# bristol_longshot__1.net
KiCad netlist of a schematic drawn in EAGLE
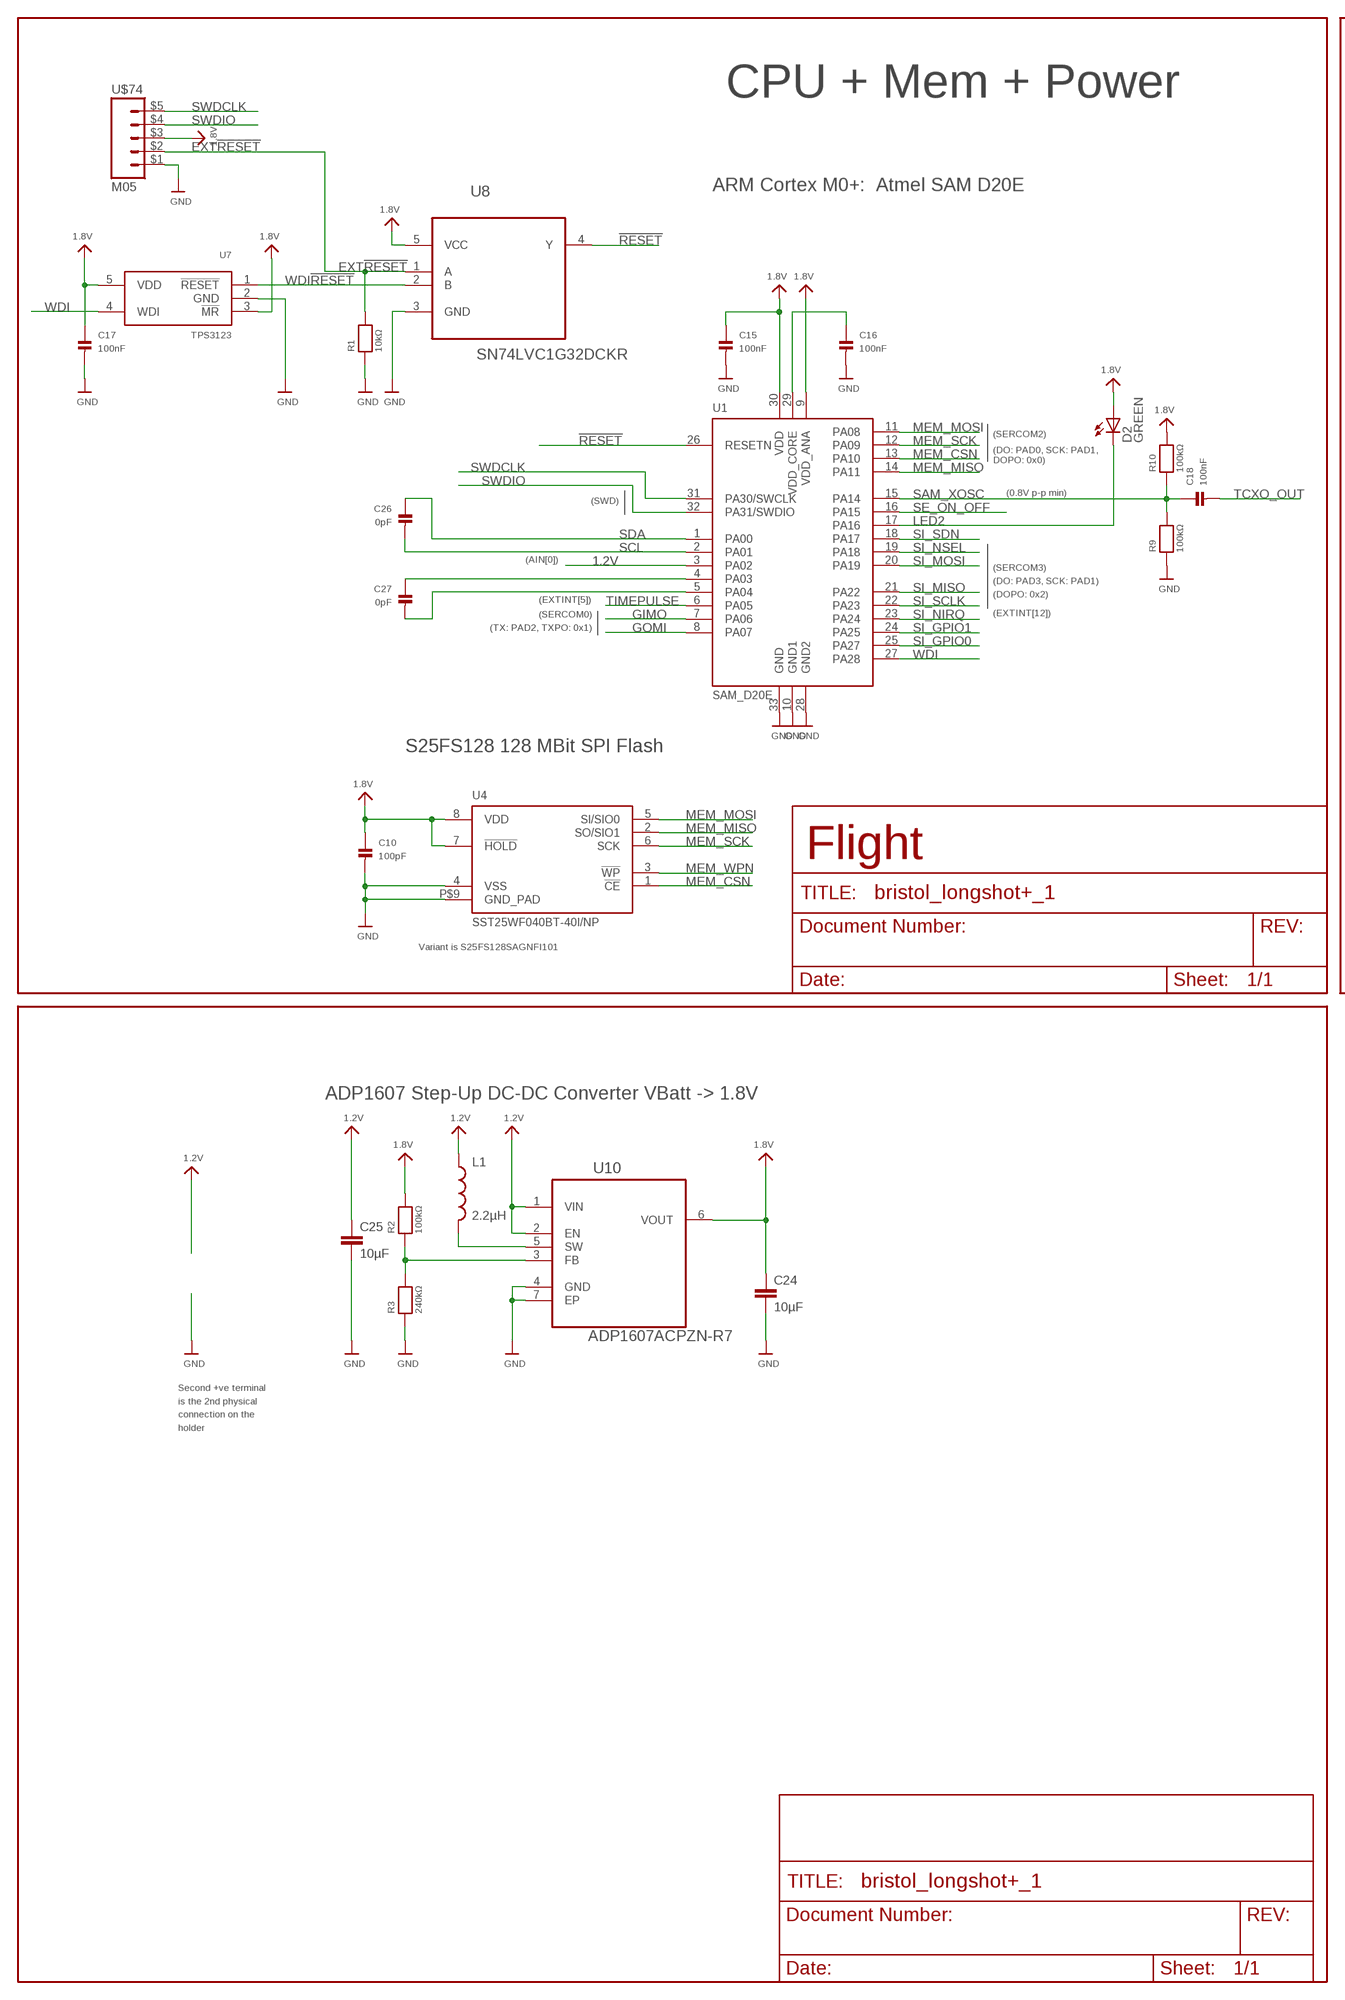
[diagram p0: schematic, sheet 1, part 1 of 2]
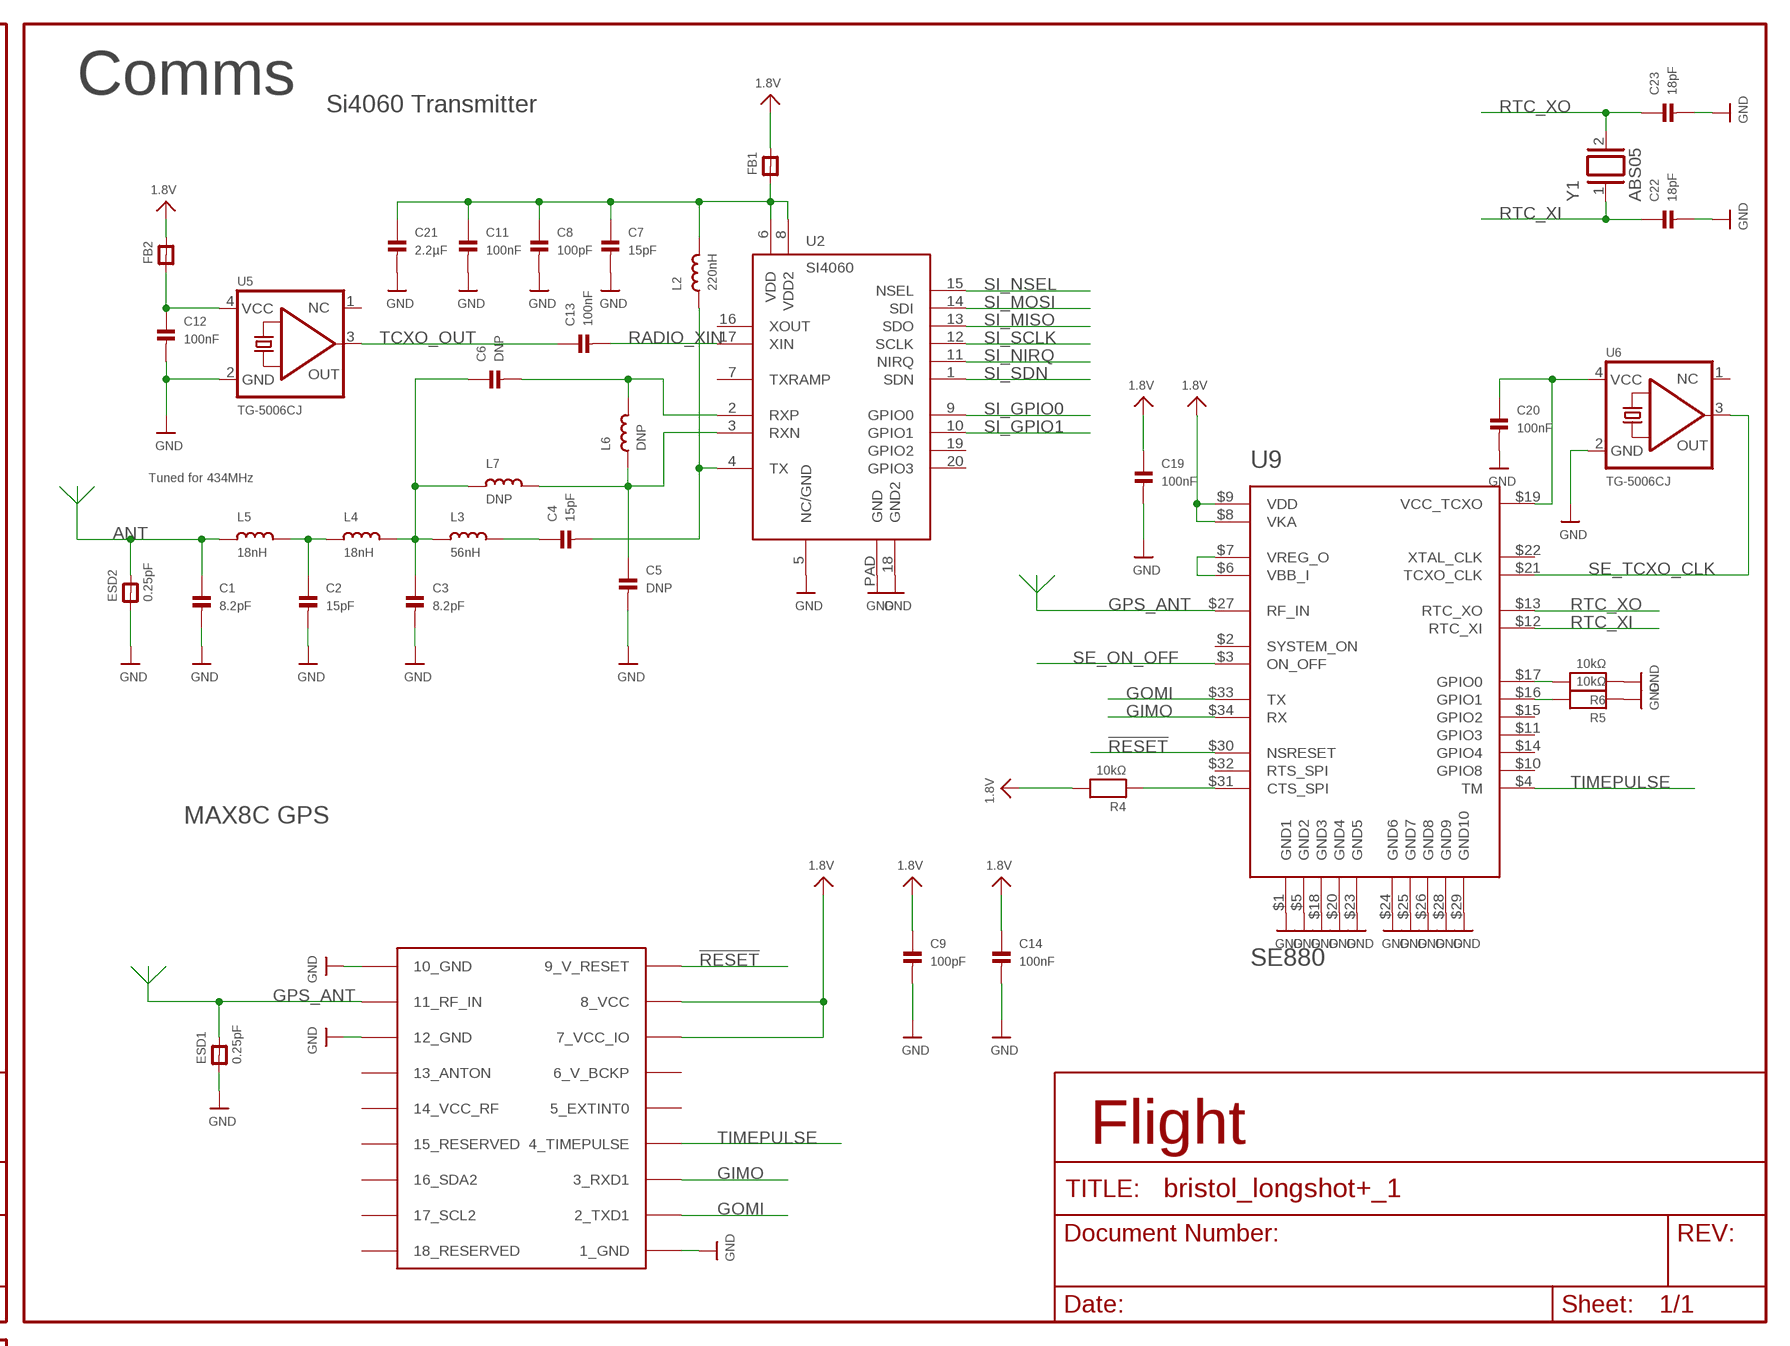
[diagram p1: schematic, sheet 1, part 2 of 2]

(export (version "E")
  (design (tool "Eeschema 10.0.6"))
  (components
    (comp (ref "C1")
      (value "8.2pF")
      (footprint "eagle-import:_0402")
      (libsource (lib "eagle-import") (part "CAP_CERAMIC_0402"))
    )
    (comp (ref "C2")
      (value "15pF")
      (footprint "eagle-import:_0402")
      (libsource (lib "eagle-import") (part "CAP_CERAMIC_0402"))
    )
    (comp (ref "C3")
      (value "8.2pF")
      (footprint "eagle-import:_0402")
      (libsource (lib "eagle-import") (part "CAP_CERAMIC_0402"))
    )
    (comp (ref "C4")
      (value "15pF")
      (footprint "eagle-import:_0402")
      (libsource (lib "eagle-import") (part "CAP_CERAMIC_0402"))
    )
    (comp (ref "C5")
      (value "DNP")
      (footprint "eagle-import:_0402")
      (libsource (lib "eagle-import") (part "CAP_CERAMIC_0402"))
    )
    (comp (ref "C6")
      (value "DNP")
      (footprint "eagle-import:_0402")
      (libsource (lib "eagle-import") (part "CAP_CERAMIC_0402"))
    )
    (comp (ref "C7")
      (value "15pF")
      (footprint "eagle-import:_0402")
      (libsource (lib "eagle-import") (part "CAP_CERAMIC_0402"))
    )
    (comp (ref "C8")
      (value "100pF")
      (footprint "eagle-import:_0402")
      (libsource (lib "eagle-import") (part "CAP_CERAMIC_0402"))
    )
    (comp (ref "C9")
      (value "100pF")
      (footprint "eagle-import:_0402")
      (libsource (lib "eagle-import") (part "CAP_CERAMIC_0402"))
    )
    (comp (ref "C10")
      (value "100pF")
      (footprint "eagle-import:_0402")
      (libsource (lib "eagle-import") (part "CAP_CERAMIC_0402"))
    )
    (comp (ref "C11")
      (value "100nF")
      (footprint "eagle-import:_0402")
      (libsource (lib "eagle-import") (part "CAP_CERAMIC_0402"))
    )
    (comp (ref "C12")
      (value "100nF")
      (footprint "eagle-import:_0402")
      (libsource (lib "eagle-import") (part "CAP_CERAMIC_0402"))
    )
    (comp (ref "C13")
      (value "100nF")
      (footprint "eagle-import:_0402")
      (libsource (lib "eagle-import") (part "CAP_CERAMIC_0402"))
    )
    (comp (ref "C14")
      (value "100nF")
      (footprint "eagle-import:_0402")
      (libsource (lib "eagle-import") (part "CAP_CERAMIC_0402"))
    )
    (comp (ref "C15")
      (value "100nF")
      (footprint "eagle-import:_0402")
      (libsource (lib "eagle-import") (part "CAP_CERAMIC_0402"))
    )
    (comp (ref "C16")
      (value "100nF")
      (footprint "eagle-import:_0402")
      (libsource (lib "eagle-import") (part "CAP_CERAMIC_0402"))
    )
    (comp (ref "C17")
      (value "100nF")
      (footprint "eagle-import:_0402")
      (libsource (lib "eagle-import") (part "CAP_CERAMIC_0402"))
    )
    (comp (ref "C18")
      (value "100nF")
      (footprint "eagle-import:_0402")
      (libsource (lib "eagle-import") (part "CAP_CERAMIC_0402"))
    )
    (comp (ref "C19")
      (value "100nF")
      (footprint "eagle-import:_0402")
      (libsource (lib "eagle-import") (part "CAP_CERAMIC_0402"))
    )
    (comp (ref "C20")
      (value "100nF")
      (footprint "eagle-import:_0402")
      (libsource (lib "eagle-import") (part "CAP_CERAMIC_0402"))
    )
    (comp (ref "C21")
      (value "2.2µF")
      (footprint "eagle-import:_0402")
      (libsource (lib "eagle-import") (part "CAP_CERAMIC_0402"))
    )
    (comp (ref "C22")
      (value "18pF")
      (footprint "eagle-import:_0402")
      (libsource (lib "eagle-import") (part "CAP_CERAMIC_0402"))
    )
    (comp (ref "C23")
      (value "18pF")
      (footprint "eagle-import:_0402")
      (libsource (lib "eagle-import") (part "CAP_CERAMIC_0402"))
    )
    (comp (ref "C24")
      (value "10µF")
      (footprint "eagle-import:C0603K")
      (libsource (lib "eagle-import") (part "C-EUC0603K"))
    )
    (comp (ref "C25")
      (value "10µF")
      (footprint "eagle-import:C0603K")
      (libsource (lib "eagle-import") (part "C-EUC0603K"))
    )
    (comp (ref "C26")
      (value "0pF")
      (footprint "eagle-import:_0402")
      (libsource (lib "eagle-import") (part "CAP_CERAMIC_0402"))
    )
    (comp (ref "C27")
      (value "0pF")
      (footprint "eagle-import:_0402")
      (libsource (lib "eagle-import") (part "CAP_CERAMIC_0402"))
    )
    (comp (ref "D2")
      (value "GREEN")
      (footprint "eagle-import:CHIPLED_0603")
      (libsource (lib "eagle-import") (part "LEDCHIPLED_0603"))
    )
    (comp (ref "ESD1")
      (value "0.25pF")
      (footprint "eagle-import:_0603MP")
      (libsource (lib "eagle-import") (part "FERRITE_0603MP"))
    )
    (comp (ref "ESD2")
      (value "0.25pF")
      (footprint "eagle-import:_0603MP")
      (libsource (lib "eagle-import") (part "FERRITE_0603MP"))
    )
    (comp (ref "FB1")
      (value "FERRITE_0402")
      (footprint "eagle-import:_0402")
      (libsource (lib "eagle-import") (part "FERRITE_0402"))
    )
    (comp (ref "FB2")
      (value "FERRITE_0402")
      (footprint "eagle-import:_0402")
      (libsource (lib "eagle-import") (part "FERRITE_0402"))
    )
    (comp (ref "L1")
      (value "2.2µH")
      (footprint "eagle-import:1007")
      (libsource (lib "eagle-import") (part "INDUCTOR1007"))
    )
    (comp (ref "L2")
      (value "220nH")
      (footprint "eagle-import:_0402")
      (libsource (lib "eagle-import") (part "INDUCTOR_0402"))
    )
    (comp (ref "L3")
      (value "56nH")
      (footprint "eagle-import:_0402")
      (libsource (lib "eagle-import") (part "INDUCTOR_0402"))
    )
    (comp (ref "L4")
      (value "18nH")
      (footprint "eagle-import:_0402")
      (libsource (lib "eagle-import") (part "INDUCTOR_0402"))
    )
    (comp (ref "L5")
      (value "18nH")
      (footprint "eagle-import:_0402")
      (libsource (lib "eagle-import") (part "INDUCTOR_0402"))
    )
    (comp (ref "L6")
      (value "DNP")
      (footprint "eagle-import:_0402")
      (libsource (lib "eagle-import") (part "INDUCTOR_0402"))
    )
    (comp (ref "L7")
      (value "DNP")
      (footprint "eagle-import:_0402")
      (libsource (lib "eagle-import") (part "INDUCTOR_0402"))
    )
    (comp (ref "R1")
      (value "10kΩ")
      (footprint "eagle-import:_0402")
      (libsource (lib "eagle-import") (part "RESISTOR_0402"))
    )
    (comp (ref "R2")
      (value "100kΩ")
      (footprint "eagle-import:_0402")
      (libsource (lib "eagle-import") (part "RESISTOR_0402"))
    )
    (comp (ref "R3")
      (value "240kΩ")
      (footprint "eagle-import:_0402")
      (libsource (lib "eagle-import") (part "RESISTOR_0402"))
    )
    (comp (ref "R4")
      (value "10kΩ")
      (footprint "eagle-import:_0402")
      (libsource (lib "eagle-import") (part "RESISTOR_0402"))
    )
    (comp (ref "R5")
      (value "10kΩ")
      (footprint "eagle-import:_0402")
      (libsource (lib "eagle-import") (part "RESISTOR_0402"))
    )
    (comp (ref "R6")
      (value "10kΩ")
      (footprint "eagle-import:_0402")
      (libsource (lib "eagle-import") (part "RESISTOR_0402"))
    )
    (comp (ref "R9")
      (value "100kΩ")
      (footprint "eagle-import:_0402")
      (libsource (lib "eagle-import") (part "RESISTOR_0402"))
    )
    (comp (ref "R10")
      (value "100kΩ")
      (footprint "eagle-import:_0402")
      (libsource (lib "eagle-import") (part "RESISTOR_0402"))
    )
    (comp (ref "U$74")
      (value "M05")
      (footprint "eagle-import:M05_SIDE")
      (libsource (lib "eagle-import") (part "M05"))
    )
    (comp (ref "U1")
      (value "SAM_D20E")
      (footprint "eagle-import:QFN32_5MM")
      (libsource (lib "eagle-import") (part "SAM_D20E"))
    )
    (comp (ref "U2")
      (value "SI4060")
      (footprint "eagle-import:QFN20")
      (libsource (lib "eagle-import") (part "SI4060"))
    )
    (comp (ref "U3")
      (value "UBLOX_MAX")
      (footprint "eagle-import:UBLOX_MAX")
      (libsource (lib "eagle-import") (part "UBLOX_MAX"))
    )
    (comp (ref "U4")
      (value "SST25WF040BT-40I/NP")
      (footprint "eagle-import:USON-8")
      (libsource (lib "eagle-import") (part "SST25WF040BT-40I/NP"))
    )
    (comp (ref "U5")
      (value "TG-5006CJ")
      (footprint "eagle-import:TC-5006CJ")
      (libsource (lib "eagle-import") (part "TG-5006CJ"))
    )
    (comp (ref "U6")
      (value "TG-5006CJ")
      (footprint "eagle-import:TC-5006CJ")
      (libsource (lib "eagle-import") (part "TG-5006CJ"))
    )
    (comp (ref "U7")
      (value "TPS3123")
      (footprint "eagle-import:SOT23-5")
      (libsource (lib "eagle-import") (part "TPS3123"))
    )
    (comp (ref "U8")
      (value "SN74LVC1G32DCKR")
      (footprint "eagle-import:SOT65P210X110-5N")
      (libsource (lib "eagle-import") (part "SN74LVC1G32DCKR"))
    )
    (comp (ref "U9")
      (value "SE880")
      (footprint "eagle-import:SE880")
      (libsource (lib "eagle-import") (part "SE880"))
    )
    (comp (ref "U10")
      (value "ADP1607ACPZN-R7")
      (footprint "eagle-import:DFN200X200X60-7N")
      (libsource (lib "eagle-import") (part "ADP1607ACPZN-R7"))
    )
    (comp (ref "Y1")
      (value "ABS05")
      (footprint "eagle-import:ABS05")
      (libsource (lib "eagle-import") (part "ABS05"))
    )
  )
  (nets
    (net (code "1") (name "/ANT") (class "Default")
      (node (ref "C1") (pin "1") (pinfunction "P$1_1") (pintype "passive"))
      (node (ref "ESD2") (pin "2") (pinfunction "P$2_2") (pintype "passive"))
      (node (ref "L5") (pin "1") (pinfunction "1_1") (pintype "passive"))
    )
    (net (code "2") (name "/EXT~{RESET}") (class "Default")
      (node (ref "R1") (pin "2") (pinfunction "2_2") (pintype "passive"))
      (node (ref "U$74") (pin "$2") (pinfunction "2_$2") (pintype "passive"))
      (node (ref "U8") (pin "1") (pinfunction "A_1") (pintype "input"))
    )
    (net (code "3") (name "/GIMO") (class "Default")
      (node (ref "U1") (pin "7") (pinfunction "PA06_7") (pintype "bidirectional"))
      (node (ref "U3") (pin "3_RXD1") (pinfunction "3_RXD1_3_RXD1") (pintype "bidirectional"))
      (node (ref "U9") (pin "$34") (pinfunction "RX_$34") (pintype "bidirectional"))
    )
    (net (code "4") (name "/GOMI") (class "Default")
      (node (ref "U1") (pin "8") (pinfunction "PA07_8") (pintype "bidirectional"))
      (node (ref "U3") (pin "2_TXD1") (pinfunction "2_TXD1_2_TXD1") (pintype "bidirectional"))
      (node (ref "U9") (pin "$33") (pinfunction "TX_$33") (pintype "bidirectional"))
    )
    (net (code "5") (name "/GPS_ANT") (class "Default")
      (node (ref "ESD1") (pin "2") (pinfunction "P$2_2") (pintype "passive"))
      (node (ref "U3") (pin "11_RF_IN") (pinfunction "11_RF_IN_11_RF_IN") (pintype "bidirectional"))
      (node (ref "U9") (pin "$27") (pinfunction "RF_IN_$27") (pintype "bidirectional"))
    )
    (net (code "6") (name "/LED2") (class "Default")
      (node (ref "D2") (pin "C") (pinfunction "C_C") (pintype "passive"))
      (node (ref "U1") (pin "17") (pinfunction "PA16_17") (pintype "bidirectional"))
    )
    (net (code "7") (name "/MEM_CSN") (class "Default")
      (node (ref "U1") (pin "13") (pinfunction "PA10_13") (pintype "bidirectional"))
      (node (ref "U4") (pin "1") (pinfunction "~{CE}_1") (pintype "input"))
    )
    (net (code "8") (name "/MEM_MISO") (class "Default")
      (node (ref "U1") (pin "14") (pinfunction "PA11_14") (pintype "bidirectional"))
      (node (ref "U4") (pin "2") (pinfunction "SO/SIO1_2") (pintype "output"))
    )
    (net (code "9") (name "/MEM_MOSI") (class "Default")
      (node (ref "U1") (pin "11") (pinfunction "PA08_11") (pintype "bidirectional"))
      (node (ref "U4") (pin "5") (pinfunction "SI/SIO0_5") (pintype "bidirectional"))
    )
    (net (code "10") (name "/MEM_SCK") (class "Default")
      (node (ref "U1") (pin "12") (pinfunction "PA09_12") (pintype "bidirectional"))
      (node (ref "U4") (pin "6") (pinfunction "SCK_6") (pintype "input"))
    )
    (net (code "11") (name "/MEM_WPN") (class "Default")
      (node (ref "U4") (pin "3") (pinfunction "~{WP}_3") (pintype "output"))
    )
    (net (code "12") (name "/RADIO_XIN") (class "Default")
      (node (ref "C13") (pin "2") (pinfunction "P$2_2") (pintype "passive"))
      (node (ref "U2") (pin "17") (pinfunction "XIN_17") (pintype "input"))
    )
    (net (code "13") (name "/RTC_XI") (class "Default")
      (node (ref "C22") (pin "1") (pinfunction "P$1_1") (pintype "passive"))
      (node (ref "U9") (pin "$12") (pinfunction "RTC_XI_$12") (pintype "bidirectional"))
      (node (ref "Y1") (pin "1") (pinfunction "1_1") (pintype "passive"))
    )
    (net (code "14") (name "/RTC_XO") (class "Default")
      (node (ref "C23") (pin "1") (pinfunction "P$1_1") (pintype "passive"))
      (node (ref "U9") (pin "$13") (pinfunction "RTC_XO_$13") (pintype "bidirectional"))
      (node (ref "Y1") (pin "2") (pinfunction "2_2") (pintype "passive"))
    )
    (net (code "15") (name "/SAM_XOSC") (class "Default")
      (node (ref "C18") (pin "1") (pinfunction "P$1_1") (pintype "passive"))
      (node (ref "R10") (pin "1") (pinfunction "1_1") (pintype "passive"))
      (node (ref "R9") (pin "2") (pinfunction "2_2") (pintype "passive"))
      (node (ref "U1") (pin "15") (pinfunction "PA14_15") (pintype "bidirectional"))
    )
    (net (code "16") (name "/SCL") (class "Default")
      (node (ref "C26") (pin "2") (pinfunction "P$2_2") (pintype "passive"))
      (node (ref "U1") (pin "2") (pinfunction "PA01_2") (pintype "bidirectional"))
    )
    (net (code "17") (name "/SDA") (class "Default")
      (node (ref "C26") (pin "1") (pinfunction "P$1_1") (pintype "passive"))
      (node (ref "U1") (pin "1") (pinfunction "PA00_1") (pintype "bidirectional"))
    )
    (net (code "18") (name "/SE_ON_OFF") (class "Default")
      (node (ref "U1") (pin "16") (pinfunction "PA15_16") (pintype "bidirectional"))
      (node (ref "U9") (pin "$3") (pinfunction "ON_OFF_$3") (pintype "bidirectional"))
    )
    (net (code "19") (name "/SE_TCXO_CLK") (class "Default")
      (node (ref "U6") (pin "3") (pinfunction "OUT_3") (pintype "output"))
      (node (ref "U9") (pin "$21") (pinfunction "TCXO_CLK_$21") (pintype "bidirectional"))
    )
    (net (code "20") (name "/SI_GPIO0") (class "Default")
      (node (ref "U1") (pin "25") (pinfunction "PA27_25") (pintype "bidirectional"))
      (node (ref "U2") (pin "9") (pinfunction "GPIO0_9") (pintype "bidirectional"))
    )
    (net (code "21") (name "/SI_GPIO1") (class "Default")
      (node (ref "U1") (pin "24") (pinfunction "PA25_24") (pintype "bidirectional"))
      (node (ref "U2") (pin "10") (pinfunction "GPIO1_10") (pintype "bidirectional"))
    )
    (net (code "22") (name "/SI_MISO") (class "Default")
      (node (ref "U1") (pin "21") (pinfunction "PA22_21") (pintype "bidirectional"))
      (node (ref "U2") (pin "13") (pinfunction "SDO_13") (pintype "output"))
    )
    (net (code "23") (name "/SI_MOSI") (class "Default")
      (node (ref "U1") (pin "20") (pinfunction "PA19_20") (pintype "bidirectional"))
      (node (ref "U2") (pin "14") (pinfunction "SDI_14") (pintype "bidirectional"))
    )
    (net (code "24") (name "/SI_NIRQ") (class "Default")
      (node (ref "U1") (pin "23") (pinfunction "PA24_23") (pintype "bidirectional"))
      (node (ref "U2") (pin "11") (pinfunction "NIRQ_11") (pintype "output"))
    )
    (net (code "25") (name "/SI_NSEL") (class "Default")
      (node (ref "U1") (pin "19") (pinfunction "PA18_19") (pintype "bidirectional"))
      (node (ref "U2") (pin "15") (pinfunction "NSEL_15") (pintype "input"))
    )
    (net (code "26") (name "/SI_SCLK") (class "Default")
      (node (ref "U1") (pin "22") (pinfunction "PA23_22") (pintype "bidirectional"))
      (node (ref "U2") (pin "12") (pinfunction "SCLK_12") (pintype "input"))
    )
    (net (code "27") (name "/SI_SDN") (class "Default")
      (node (ref "U1") (pin "18") (pinfunction "PA17_18") (pintype "bidirectional"))
      (node (ref "U2") (pin "1") (pinfunction "SDN_1") (pintype "input"))
    )
    (net (code "28") (name "/SWDCLK") (class "Default")
      (node (ref "U$74") (pin "$5") (pinfunction "5_$5") (pintype "passive"))
      (node (ref "U1") (pin "31") (pinfunction "PA30/SWCLK_31") (pintype "bidirectional"))
    )
    (net (code "29") (name "/SWDIO") (class "Default")
      (node (ref "U$74") (pin "$4") (pinfunction "4_$4") (pintype "passive"))
      (node (ref "U1") (pin "32") (pinfunction "PA31/SWDIO_32") (pintype "bidirectional"))
    )
    (net (code "30") (name "/TCXO_OUT") (class "Default")
      (node (ref "C13") (pin "1") (pinfunction "P$1_1") (pintype "passive"))
      (node (ref "C18") (pin "2") (pinfunction "P$2_2") (pintype "passive"))
      (node (ref "U5") (pin "3") (pinfunction "OUT_3") (pintype "output"))
    )
    (net (code "31") (name "/TIMEPULSE") (class "Default")
      (node (ref "U1") (pin "6") (pinfunction "PA05_6") (pintype "bidirectional"))
      (node (ref "U3") (pin "4_TIMEPULSE") (pinfunction "4_TIMEPULSE_4_TIMEPULSE") (pintype "bidirectional"))
      (node (ref "U9") (pin "$4") (pinfunction "TM_$4") (pintype "bidirectional"))
    )
    (net (code "32") (name "/WDI") (class "Default")
      (node (ref "U1") (pin "27") (pinfunction "PA28_27") (pintype "bidirectional"))
      (node (ref "U7") (pin "4") (pinfunction "WDI_4") (pintype "bidirectional"))
    )
    (net (code "33") (name "/WDI~{RESET}") (class "Default")
      (node (ref "U7") (pin "1") (pinfunction "~{RESET}_1") (pintype "bidirectional"))
      (node (ref "U8") (pin "2") (pinfunction "B_2") (pintype "input"))
    )
    (net (code "34") (name "/~{RESET}") (class "Default")
      (node (ref "U1") (pin "26") (pinfunction "RESETN_26") (pintype "input"))
      (node (ref "U3") (pin "9_V_RESET") (pinfunction "9_V_RESET_9_V_RESET") (pintype "power_in"))
      (node (ref "U8") (pin "4") (pinfunction "Y_4") (pintype "output"))
      (node (ref "U9") (pin "$30") (pinfunction "NSRESET_$30") (pintype "bidirectional"))
    )
    (net (code "35") (name "1.2V") (class "Default")
      (node (ref "C25") (pin "1") (pinfunction "1_1") (pintype "passive"))
      (node (ref "L1") (pin "1") (pinfunction "1_1") (pintype "passive"))
      (node (ref "U1") (pin "3") (pinfunction "PA02_3") (pintype "bidirectional"))
      (node (ref "U10") (pin "1") (pinfunction "VIN_1") (pintype "power_in"))
      (node (ref "U10") (pin "2") (pinfunction "EN_2") (pintype "input"))
    )
    (net (code "36") (name "1.8V") (class "Default")
      (node (ref "C10") (pin "1") (pinfunction "P$1_1") (pintype "passive"))
      (node (ref "C14") (pin "1") (pinfunction "P$1_1") (pintype "passive"))
      (node (ref "C15") (pin "1") (pinfunction "P$1_1") (pintype "passive"))
      (node (ref "C17") (pin "1") (pinfunction "P$1_1") (pintype "passive"))
      (node (ref "C19") (pin "1") (pinfunction "P$1_1") (pintype "passive"))
      (node (ref "C24") (pin "1") (pinfunction "1_1") (pintype "passive"))
      (node (ref "C9") (pin "1") (pinfunction "P$1_1") (pintype "passive"))
      (node (ref "D2") (pin "A") (pinfunction "A_A") (pintype "passive"))
      (node (ref "FB1") (pin "2") (pinfunction "P$2_2") (pintype "passive"))
      (node (ref "FB2") (pin "2") (pinfunction "P$2_2") (pintype "passive"))
      (node (ref "R10") (pin "2") (pinfunction "2_2") (pintype "passive"))
      (node (ref "R2") (pin "2") (pinfunction "2_2") (pintype "passive"))
      (node (ref "R4") (pin "2") (pinfunction "2_2") (pintype "passive"))
      (node (ref "U$74") (pin "$3") (pinfunction "3_$3") (pintype "passive"))
      (node (ref "U1") (pin "30") (pinfunction "VDD_30") (pintype "power_in"))
      (node (ref "U1") (pin "9") (pinfunction "VDD_ANA_9") (pintype "power_in"))
      (node (ref "U10") (pin "6") (pinfunction "VOUT_6") (pintype "output"))
      (node (ref "U3") (pin "7_VCC_IO") (pinfunction "7_VCC_IO_7_VCC_IO") (pintype "power_in"))
      (node (ref "U3") (pin "8_VCC") (pinfunction "8_VCC_8_VCC") (pintype "power_in"))
      (node (ref "U4") (pin "7") (pinfunction "~{HOLD}_7") (pintype "output"))
      (node (ref "U4") (pin "8") (pinfunction "VDD_8") (pintype "power_in"))
      (node (ref "U7") (pin "3") (pinfunction "~{MR}_3") (pintype "bidirectional"))
      (node (ref "U7") (pin "5") (pinfunction "VDD_5") (pintype "bidirectional"))
      (node (ref "U8") (pin "5") (pinfunction "VCC_5") (pintype "power_in"))
      (node (ref "U9") (pin "$8") (pinfunction "VKA_$8") (pintype "bidirectional"))
      (node (ref "U9") (pin "$9") (pinfunction "VDD_$9") (pintype "bidirectional"))
    )
    (net (code "37") (name "GND") (class "Default")
      (node (ref "C1") (pin "2") (pinfunction "P$2_2") (pintype "passive"))
      (node (ref "C10") (pin "2") (pinfunction "P$2_2") (pintype "passive"))
      (node (ref "C11") (pin "2") (pinfunction "P$2_2") (pintype "passive"))
      (node (ref "C12") (pin "2") (pinfunction "P$2_2") (pintype "passive"))
      (node (ref "C14") (pin "2") (pinfunction "P$2_2") (pintype "passive"))
      (node (ref "C15") (pin "2") (pinfunction "P$2_2") (pintype "passive"))
      (node (ref "C16") (pin "2") (pinfunction "P$2_2") (pintype "passive"))
      (node (ref "C17") (pin "2") (pinfunction "P$2_2") (pintype "passive"))
      (node (ref "C19") (pin "2") (pinfunction "P$2_2") (pintype "passive"))
      (node (ref "C2") (pin "2") (pinfunction "P$2_2") (pintype "passive"))
      (node (ref "C20") (pin "2") (pinfunction "P$2_2") (pintype "passive"))
      (node (ref "C21") (pin "2") (pinfunction "P$2_2") (pintype "passive"))
      (node (ref "C22") (pin "2") (pinfunction "P$2_2") (pintype "passive"))
      (node (ref "C23") (pin "2") (pinfunction "P$2_2") (pintype "passive"))
      (node (ref "C24") (pin "2") (pinfunction "2_2") (pintype "passive"))
      (node (ref "C25") (pin "2") (pinfunction "2_2") (pintype "passive"))
      (node (ref "C3") (pin "2") (pinfunction "P$2_2") (pintype "passive"))
      (node (ref "C5") (pin "2") (pinfunction "P$2_2") (pintype "passive"))
      (node (ref "C7") (pin "2") (pinfunction "P$2_2") (pintype "passive"))
      (node (ref "C8") (pin "2") (pinfunction "P$2_2") (pintype "passive"))
      (node (ref "C9") (pin "2") (pinfunction "P$2_2") (pintype "passive"))
      (node (ref "ESD1") (pin "1") (pinfunction "P$1_1") (pintype "passive"))
      (node (ref "ESD2") (pin "1") (pinfunction "P$1_1") (pintype "passive"))
      (node (ref "R1") (pin "1") (pinfunction "1_1") (pintype "passive"))
      (node (ref "R3") (pin "1") (pinfunction "1_1") (pintype "passive"))
      (node (ref "R5") (pin "1") (pinfunction "1_1") (pintype "passive"))
      (node (ref "R6") (pin "1") (pinfunction "1_1") (pintype "passive"))
      (node (ref "R9") (pin "1") (pinfunction "1_1") (pintype "passive"))
      (node (ref "U$74") (pin "$1") (pinfunction "1_$1") (pintype "passive"))
      (node (ref "U1") (pin "10") (pinfunction "GND1_10") (pintype "power_in"))
      (node (ref "U1") (pin "28") (pinfunction "GND2_28") (pintype "power_in"))
      (node (ref "U1") (pin "33") (pinfunction "GND_33") (pintype "power_in"))
      (node (ref "U10") (pin "4") (pinfunction "GND_4") (pintype "power_in"))
      (node (ref "U10") (pin "7") (pinfunction "EP_7") (pintype "passive"))
      (node (ref "U2") (pin "18") (pinfunction "GND2_18") (pintype "power_in"))
      (node (ref "U2") (pin "5") (pinfunction "NC/GND_5") (pintype "bidirectional"))
      (node (ref "U2") (pin "PAD") (pinfunction "GND_PAD") (pintype "power_in"))
      (node (ref "U3") (pin "10_GND") (pinfunction "10_GND_10_GND") (pintype "power_in"))
      (node (ref "U3") (pin "12_GND") (pinfunction "12_GND_12_GND") (pintype "power_in"))
      (node (ref "U3") (pin "1_GND") (pinfunction "1_GND_1_GND") (pintype "power_in"))
      (node (ref "U4") (pin "4") (pinfunction "VSS_4") (pintype "power_in"))
      (node (ref "U4") (pin "P$9") (pinfunction "GND_PAD_P$9") (pintype "power_in"))
      (node (ref "U5") (pin "2") (pinfunction "GND_2") (pintype "power_in"))
      (node (ref "U6") (pin "2") (pinfunction "GND_2") (pintype "power_in"))
      (node (ref "U7") (pin "2") (pinfunction "GND_2") (pintype "bidirectional"))
      (node (ref "U8") (pin "3") (pinfunction "GND_3") (pintype "passive"))
      (node (ref "U9") (pin "$1") (pinfunction "GND1_$1") (pintype "bidirectional"))
      (node (ref "U9") (pin "$18") (pinfunction "GND3_$18") (pintype "bidirectional"))
      (node (ref "U9") (pin "$20") (pinfunction "GND4_$20") (pintype "bidirectional"))
      (node (ref "U9") (pin "$23") (pinfunction "GND5_$23") (pintype "bidirectional"))
      (node (ref "U9") (pin "$24") (pinfunction "GND6_$24") (pintype "bidirectional"))
      (node (ref "U9") (pin "$25") (pinfunction "GND7_$25") (pintype "bidirectional"))
      (node (ref "U9") (pin "$26") (pinfunction "GND8_$26") (pintype "bidirectional"))
      (node (ref "U9") (pin "$28") (pinfunction "GND9_$28") (pintype "bidirectional"))
      (node (ref "U9") (pin "$29") (pinfunction "GND10_$29") (pintype "bidirectional"))
      (node (ref "U9") (pin "$5") (pinfunction "GND2_$5") (pintype "bidirectional"))
    )
    (net (code "38") (name "Net-(C2-P$1)") (class "Default")
      (node (ref "C2") (pin "1") (pinfunction "P$1_1") (pintype "passive"))
      (node (ref "L4") (pin "1") (pinfunction "1_1") (pintype "passive"))
      (node (ref "L5") (pin "2") (pinfunction "2_2") (pintype "passive"))
    )
    (net (code "39") (name "Net-(C3-P$1)") (class "Default")
      (node (ref "C3") (pin "1") (pinfunction "P$1_1") (pintype "passive"))
      (node (ref "C6") (pin "1") (pinfunction "P$1_1") (pintype "passive"))
      (node (ref "L3") (pin "1") (pinfunction "1_1") (pintype "passive"))
      (node (ref "L4") (pin "2") (pinfunction "2_2") (pintype "passive"))
      (node (ref "L7") (pin "1") (pinfunction "1_1") (pintype "passive"))
    )
    (net (code "40") (name "Net-(C4-P$1)") (class "Default")
      (node (ref "C4") (pin "1") (pinfunction "P$1_1") (pintype "passive"))
      (node (ref "L3") (pin "2") (pinfunction "2_2") (pintype "passive"))
    )
    (net (code "41") (name "Net-(C4-P$2)") (class "Default")
      (node (ref "C4") (pin "2") (pinfunction "P$2_2") (pintype "passive"))
      (node (ref "L2") (pin "1") (pinfunction "1_1") (pintype "passive"))
      (node (ref "U2") (pin "4") (pinfunction "TX_4") (pintype "output"))
    )
    (net (code "42") (name "Net-(C5-P$1)") (class "Default")
      (node (ref "C5") (pin "1") (pinfunction "P$1_1") (pintype "passive"))
      (node (ref "L6") (pin "1") (pinfunction "1_1") (pintype "passive"))
      (node (ref "L7") (pin "2") (pinfunction "2_2") (pintype "passive"))
      (node (ref "U2") (pin "3") (pinfunction "RXN_3") (pintype "input"))
    )
    (net (code "43") (name "Net-(C6-P$2)") (class "Default")
      (node (ref "C6") (pin "2") (pinfunction "P$2_2") (pintype "passive"))
      (node (ref "L6") (pin "2") (pinfunction "2_2") (pintype "passive"))
      (node (ref "U2") (pin "2") (pinfunction "RXP_2") (pintype "input"))
    )
    (net (code "44") (name "Net-(C11-P$1)") (class "Default")
      (node (ref "C11") (pin "1") (pinfunction "P$1_1") (pintype "passive"))
      (node (ref "C21") (pin "1") (pinfunction "P$1_1") (pintype "passive"))
      (node (ref "C7") (pin "1") (pinfunction "P$1_1") (pintype "passive"))
      (node (ref "C8") (pin "1") (pinfunction "P$1_1") (pintype "passive"))
      (node (ref "FB1") (pin "1") (pinfunction "P$1_1") (pintype "passive"))
      (node (ref "L2") (pin "2") (pinfunction "2_2") (pintype "passive"))
      (node (ref "U2") (pin "6") (pinfunction "VDD_6") (pintype "power_in"))
      (node (ref "U2") (pin "8") (pinfunction "VDD2_8") (pintype "power_in"))
    )
    (net (code "45") (name "Net-(C12-P$1)") (class "Default")
      (node (ref "C12") (pin "1") (pinfunction "P$1_1") (pintype "passive"))
      (node (ref "FB2") (pin "1") (pinfunction "P$1_1") (pintype "passive"))
      (node (ref "U5") (pin "4") (pinfunction "VCC_4") (pintype "power_in"))
    )
    (net (code "46") (name "Net-(C16-P$1)") (class "Default")
      (node (ref "C16") (pin "1") (pinfunction "P$1_1") (pintype "passive"))
      (node (ref "U1") (pin "29") (pinfunction "VDD_CORE_29") (pintype "power_in"))
    )
    (net (code "47") (name "Net-(C20-P$1)") (class "Default")
      (node (ref "C20") (pin "1") (pinfunction "P$1_1") (pintype "passive"))
      (node (ref "U6") (pin "4") (pinfunction "VCC_4") (pintype "power_in"))
      (node (ref "U9") (pin "$19") (pinfunction "VCC_TCXO_$19") (pintype "bidirectional"))
    )
    (net (code "48") (name "Net-(C27-P$1)") (class "Default")
      (node (ref "C27") (pin "1") (pinfunction "P$1_1") (pintype "passive"))
      (node (ref "U1") (pin "4") (pinfunction "PA03_4") (pintype "bidirectional"))
    )
    (net (code "49") (name "Net-(C27-P$2)") (class "Default")
      (node (ref "C27") (pin "2") (pinfunction "P$2_2") (pintype "passive"))
      (node (ref "U1") (pin "5") (pinfunction "PA04_5") (pintype "bidirectional"))
    )
    (net (code "50") (name "Net-(U9-CTS_SPI)") (class "Default")
      (node (ref "R4") (pin "1") (pinfunction "1_1") (pintype "passive"))
      (node (ref "U9") (pin "$31") (pinfunction "CTS_SPI_$31") (pintype "bidirectional"))
    )
    (net (code "51") (name "Net-(U9-GPIO0)") (class "Default")
      (node (ref "R6") (pin "2") (pinfunction "2_2") (pintype "passive"))
      (node (ref "U9") (pin "$17") (pinfunction "GPIO0_$17") (pintype "bidirectional"))
    )
    (net (code "52") (name "Net-(U9-GPIO1)") (class "Default")
      (node (ref "R5") (pin "2") (pinfunction "2_2") (pintype "passive"))
      (node (ref "U9") (pin "$16") (pinfunction "GPIO1_$16") (pintype "bidirectional"))
    )
    (net (code "53") (name "Net-(U9-VBB_I)") (class "Default")
      (node (ref "U9") (pin "$6") (pinfunction "VBB_I_$6") (pintype "bidirectional"))
      (node (ref "U9") (pin "$7") (pinfunction "VREG_O_$7") (pintype "bidirectional"))
    )
    (net (code "54") (name "Net-(U10-FB)") (class "Default")
      (node (ref "R2") (pin "1") (pinfunction "1_1") (pintype "passive"))
      (node (ref "R3") (pin "2") (pinfunction "2_2") (pintype "passive"))
      (node (ref "U10") (pin "3") (pinfunction "FB_3") (pintype "passive"))
    )
    (net (code "55") (name "Net-(U10-SW)") (class "Default")
      (node (ref "L1") (pin "2") (pinfunction "2_2") (pintype "passive"))
      (node (ref "U10") (pin "5") (pinfunction "SW_5") (pintype "passive"))
    )
    (net (code "56") (name "unconnected-(U2-GPIO2-Pad19)") (class "Default")
      (node (ref "U2") (pin "19") (pinfunction "GPIO2_19") (pintype "bidirectional"))
    )
    (net (code "57") (name "unconnected-(U2-GPIO3-Pad20)") (class "Default")
      (node (ref "U2") (pin "20") (pinfunction "GPIO3_20") (pintype "bidirectional"))
    )
    (net (code "58") (name "unconnected-(U2-TXRAMP-Pad7)") (class "Default")
      (node (ref "U2") (pin "7") (pinfunction "TXRAMP_7") (pintype "bidirectional"))
    )
    (net (code "59") (name "unconnected-(U2-XOUT-Pad16)") (class "Default")
      (node (ref "U2") (pin "16") (pinfunction "XOUT_16") (pintype "output"))
    )
    (net (code "60") (name "unconnected-(U3-Pad5_EXTINT0)") (class "Default")
      (node (ref "U3") (pin "5_EXTINT0") (pinfunction "5_EXTINT0_5_EXTINT0") (pintype "bidirectional"))
    )
    (net (code "61") (name "unconnected-(U3-Pad6_V_BCKP)") (class "Default")
      (node (ref "U3") (pin "6_V_BCKP") (pinfunction "6_V_BCKP_6_V_BCKP") (pintype "bidirectional"))
    )
    (net (code "62") (name "unconnected-(U3-Pad13_ANTON)") (class "Default")
      (node (ref "U3") (pin "13_ANTON") (pinfunction "13_ANTON_13_ANTON") (pintype "bidirectional"))
    )
    (net (code "63") (name "unconnected-(U3-Pad14_VCC_RF)") (class "Default")
      (node (ref "U3") (pin "14_VCC_RF") (pinfunction "14_VCC_RF_14_VCC_RF") (pintype "bidirectional"))
    )
    (net (code "64") (name "unconnected-(U3-Pad15_RESERVED)") (class "Default")
      (node (ref "U3") (pin "15_RESERVED") (pinfunction "15_RESERVED_15_RESERVED") (pintype "bidirectional"))
    )
    (net (code "65") (name "unconnected-(U3-Pad16_SDA2)") (class "Default")
      (node (ref "U3") (pin "16_SDA2") (pinfunction "16_SDA2_16_SDA2") (pintype "bidirectional"))
    )
    (net (code "66") (name "unconnected-(U3-Pad17_SCL2)") (class "Default")
      (node (ref "U3") (pin "17_SCL2") (pinfunction "17_SCL2_17_SCL2") (pintype "bidirectional"))
    )
    (net (code "67") (name "unconnected-(U3-Pad18_RESERVED)") (class "Default")
      (node (ref "U3") (pin "18_RESERVED") (pinfunction "18_RESERVED_18_RESERVED") (pintype "bidirectional"))
    )
    (net (code "68") (name "unconnected-(U5-NC-Pad1)") (class "Default")
      (node (ref "U5") (pin "1") (pinfunction "NC_1") (pintype "no_connect"))
    )
    (net (code "69") (name "unconnected-(U6-NC-Pad1)") (class "Default")
      (node (ref "U6") (pin "1") (pinfunction "NC_1") (pintype "no_connect"))
    )
    (net (code "70") (name "unconnected-(U9-GPIO2-Pad$15)") (class "Default")
      (node (ref "U9") (pin "$15") (pinfunction "GPIO2_$15") (pintype "bidirectional"))
    )
    (net (code "71") (name "unconnected-(U9-GPIO3-Pad$11)") (class "Default")
      (node (ref "U9") (pin "$11") (pinfunction "GPIO3_$11") (pintype "bidirectional"))
    )
    (net (code "72") (name "unconnected-(U9-GPIO4-Pad$14)") (class "Default")
      (node (ref "U9") (pin "$14") (pinfunction "GPIO4_$14") (pintype "bidirectional"))
    )
    (net (code "73") (name "unconnected-(U9-GPIO8-Pad$10)") (class "Default")
      (node (ref "U9") (pin "$10") (pinfunction "GPIO8_$10") (pintype "bidirectional"))
    )
    (net (code "74") (name "unconnected-(U9-RTS_SPI-Pad$32)") (class "Default")
      (node (ref "U9") (pin "$32") (pinfunction "RTS_SPI_$32") (pintype "bidirectional"))
    )
    (net (code "75") (name "unconnected-(U9-SYSTEM_ON-Pad$2)") (class "Default")
      (node (ref "U9") (pin "$2") (pinfunction "SYSTEM_ON_$2") (pintype "bidirectional"))
    )
    (net (code "76") (name "unconnected-(U9-XTAL_CLK-Pad$22)") (class "Default")
      (node (ref "U9") (pin "$22") (pinfunction "XTAL_CLK_$22") (pintype "bidirectional"))
    )
  )
)
